# Sheet1.net
KiCad netlist of a schematic drawn in Altium Designer
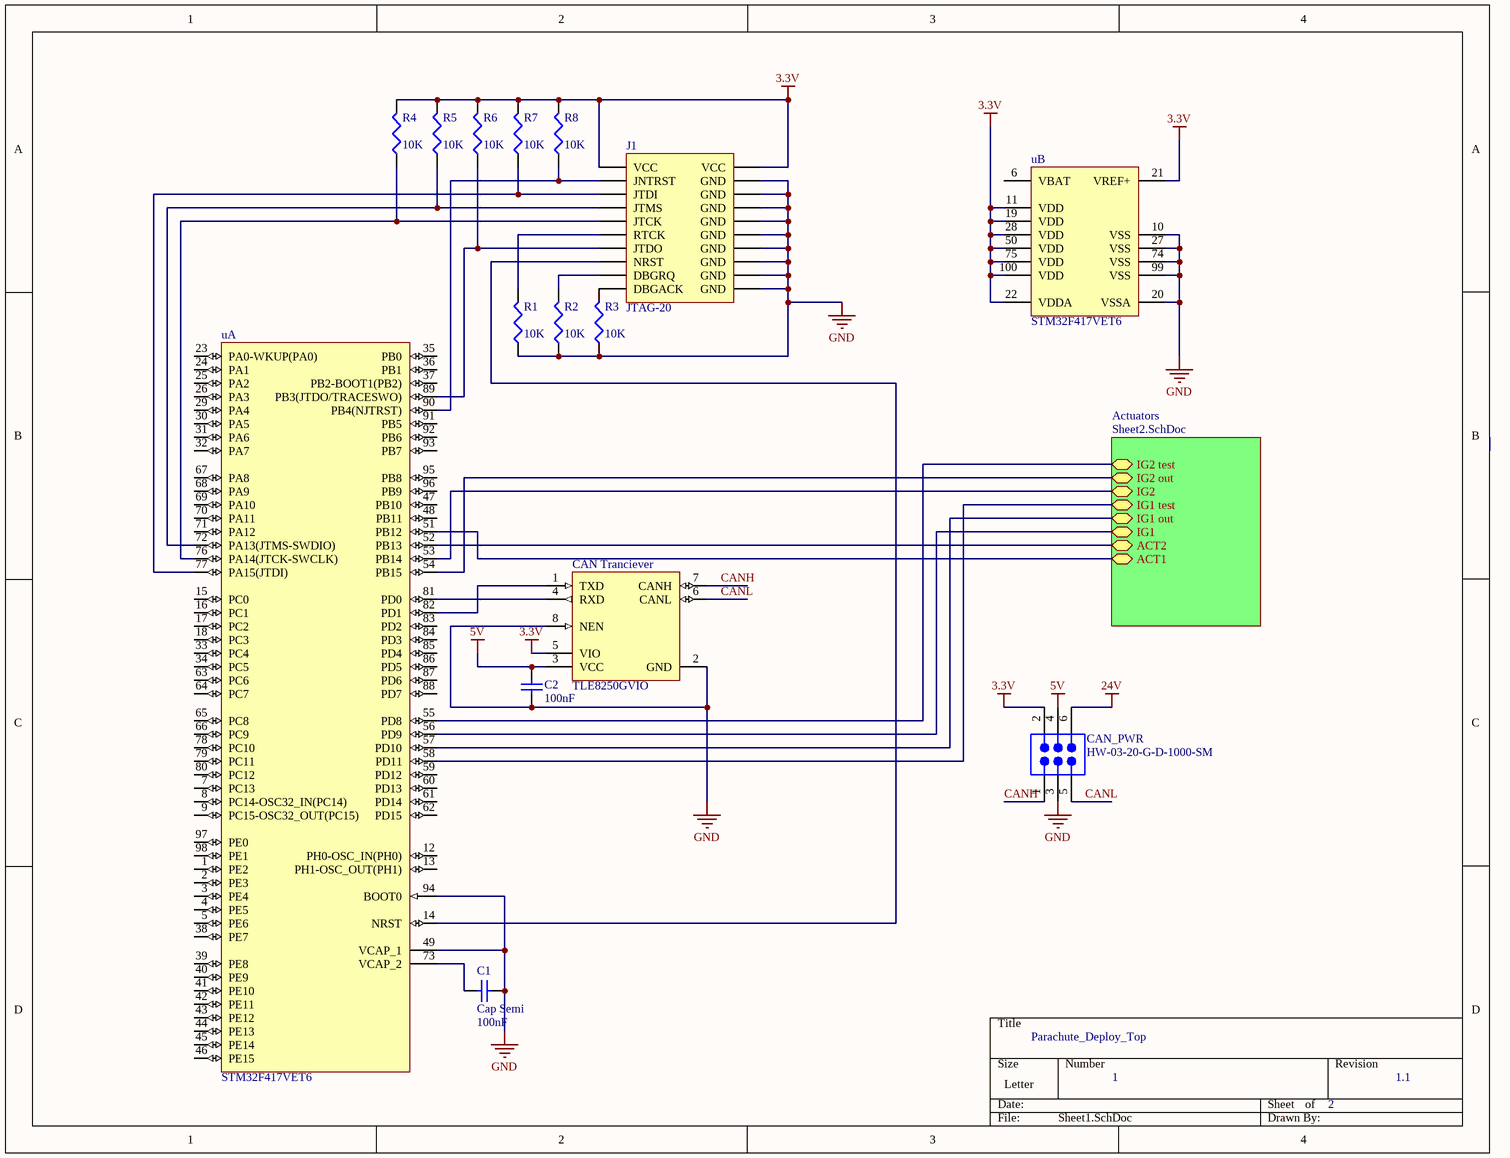
[diagram p0: Sheet1.SchDoc]

(export (version "E")
  (design (tool "Eeschema 10.0.6"))
  (components
    (comp (ref "C1")
      (value "Cap Semi")
      (footprint "C1206")
      (description "Capacitor (Semiconductor SIM Model)")
      (fields (field (name "ALTIUM_VALUE") "100nF") (field (name "PUBLISHER") "Altium Limited"))
      (libsource (lib "Miscellaneous Devices") (part "Cap Semi"))
    )
    (comp (ref "C2")
      (value "100nF")
      (footprint "C1206")
      (description "Capacitor (Semiconductor SIM Model)")
      (fields (field (name "Comment") "Cap Semi") (field (name "PUBLISHER") "Altium Limited"))
      (libsource (lib "Miscellaneous Devices") (part "Cap Semi"))
    )
    (comp (ref "CAN Tranciever")
      (value "TLE8250GVIO")
      (footprint "INF-PG-DSO-8-16_N")
      (description "High Speed CAN-Transceiver, 1 Mbit/s Transmission Rate, PG-DSO-8-16, Reel, Green")
      (fields (field (name "MANUFACTURER") "Infineon"))
      (libsource (lib "Infineon_Transceiver") (part "TLE8250GVIO"))
    )
    (comp (ref "CAN_PWR")
      (value "HW-03-20-G-D-1000-SM")
      (footprint "SMTC-HW-03-20-X-D-1000-SM")
      (fields (field (name "MANUFACTURER") "Samtec"))
      (libsource (lib "Samtec_2,54_mm_Pitch_Terminal_Strips") (part "HW-03-20-G-D-1000-SM"))
    )
    (comp (ref "J1")
      (value "JTAG-20")
      (footprint "PCBComponent_1")
      (description "20-pin JTAG header")
      (libsource (lib "Rocket_Connectors") (part "HEADER 10X2"))
    )
    (comp (ref "R1")
      (value "10K")
      (footprint "J1-0603")
      (description "Resistor")
      (fields (field (name "Comment") "RTCK PD") (field (name "PUBLISHER") "Altium Limited"))
      (libsource (lib "Miscellaneous Devices") (part "Res3"))
    )
    (comp (ref "R2")
      (value "10K")
      (footprint "J1-0603")
      (description "Resistor")
      (fields (field (name "Comment") "DBGRQ PD") (field (name "PUBLISHER") "Altium Limited"))
      (libsource (lib "Miscellaneous Devices") (part "Res3"))
    )
    (comp (ref "R3")
      (value "10K")
      (footprint "J1-0603")
      (description "Resistor")
      (fields (field (name "Comment") "DBGACK PD") (field (name "PUBLISHER") "Altium Limited"))
      (libsource (lib "Miscellaneous Devices") (part "Res3"))
    )
    (comp (ref "R4")
      (value "10K")
      (footprint "J1-0603")
      (description "Resistor")
      (fields (field (name "Comment") "RTCK PD") (field (name "PUBLISHER") "Altium Limited"))
      (libsource (lib "Miscellaneous Devices") (part "Res3"))
    )
    (comp (ref "R5")
      (value "10K")
      (footprint "J1-0603")
      (description "Resistor")
      (fields (field (name "Comment") "RTCK PD") (field (name "PUBLISHER") "Altium Limited"))
      (libsource (lib "Miscellaneous Devices") (part "Res3"))
    )
    (comp (ref "R6")
      (value "10K")
      (footprint "J1-0603")
      (description "Resistor")
      (fields (field (name "Comment") "RTCK PD") (field (name "PUBLISHER") "Altium Limited"))
      (libsource (lib "Miscellaneous Devices") (part "Res3"))
    )
    (comp (ref "R7")
      (value "10K")
      (footprint "J1-0603")
      (description "Resistor")
      (fields (field (name "Comment") "RTCK PD") (field (name "PUBLISHER") "Altium Limited"))
      (libsource (lib "Miscellaneous Devices") (part "Res3"))
    )
    (comp (ref "R8")
      (value "10K")
      (footprint "J1-0603")
      (description "Resistor")
      (fields (field (name "Comment") "RTCK PD") (field (name "PUBLISHER") "Altium Limited"))
      (libsource (lib "Miscellaneous Devices") (part "Res3"))
    )
    (comp (ref "u")
      (value "STM32F417VET6")
      (footprint "STM-LQFP100_N")
      (fields (field (name "MANUFACTURER") "STMicroelectronics"))
      (libsource (lib "STMicroelectronics STM32 F4") (part "STM32F417VET6"))
    )
  )
  (nets
    (net (code "1") (name "/ACT1") (class "Default")
      (node (ref "u") (pin "51") (pinfunction "PB12_51") (pintype "bidirectional"))
    )
    (net (code "2") (name "/ACT2") (class "Default")
      (node (ref "u") (pin "52") (pinfunction "PB13_52") (pintype "bidirectional"))
    )
    (net (code "3") (name "/CANH") (class "Default")
      (node (ref "CAN Tranciever") (pin "7") (pinfunction "CANH_7") (pintype "bidirectional"))
      (node (ref "CAN_PWR") (pin "1") (pinfunction "1_1") (pintype "passive"))
    )
    (net (code "4") (name "/CANL") (class "Default")
      (node (ref "CAN Tranciever") (pin "6") (pinfunction "CANL_6") (pintype "bidirectional"))
      (node (ref "CAN_PWR") (pin "5") (pinfunction "5_5") (pintype "passive"))
    )
    (net (code "5") (name "/IG1") (class "Default")
      (node (ref "u") (pin "56") (pinfunction "PD9_56") (pintype "bidirectional"))
    )
    (net (code "6") (name "/IG1 out") (class "Default")
      (node (ref "u") (pin "57") (pinfunction "PD10_57") (pintype "bidirectional"))
    )
    (net (code "7") (name "/IG1 test") (class "Default")
      (node (ref "u") (pin "58") (pinfunction "PD11_58") (pintype "bidirectional"))
    )
    (net (code "8") (name "/IG2") (class "Default")
      (node (ref "u") (pin "53") (pinfunction "PB14_53") (pintype "bidirectional"))
    )
    (net (code "9") (name "/IG2 out") (class "Default")
      (node (ref "u") (pin "54") (pinfunction "PB15_54") (pintype "bidirectional"))
    )
    (net (code "10") (name "/IG2 test") (class "Default")
      (node (ref "u") (pin "55") (pinfunction "PD8_55") (pintype "bidirectional"))
    )
    (net (code "11") (name "3.3V") (class "Default")
      (node (ref "CAN Tranciever") (pin "5") (pinfunction "VIO_5") (pintype "power_in"))
      (node (ref "CAN_PWR") (pin "2") (pinfunction "2_2") (pintype "passive"))
      (node (ref "J1") (pin "1") (pinfunction "VCC_1") (pintype "passive"))
      (node (ref "J1") (pin "2") (pinfunction "VCC_2") (pintype "passive"))
      (node (ref "R4") (pin "2") (pinfunction "2_2") (pintype "passive"))
      (node (ref "R5") (pin "2") (pinfunction "2_2") (pintype "passive"))
      (node (ref "R6") (pin "2") (pinfunction "2_2") (pintype "passive"))
      (node (ref "R7") (pin "2") (pinfunction "2_2") (pintype "passive"))
      (node (ref "R8") (pin "2") (pinfunction "2_2") (pintype "passive"))
      (node (ref "u") (pin "100") (pinfunction "VDD_100") (pintype "power_in"))
      (node (ref "u") (pin "11") (pinfunction "VDD_11") (pintype "power_in"))
      (node (ref "u") (pin "19") (pinfunction "VDD_19") (pintype "power_in"))
      (node (ref "u") (pin "21") (pinfunction "VREF+_21") (pintype "power_in"))
      (node (ref "u") (pin "22") (pinfunction "VDDA_22") (pintype "power_in"))
      (node (ref "u") (pin "28") (pinfunction "VDD_28") (pintype "power_in"))
      (node (ref "u") (pin "50") (pinfunction "VDD_50") (pintype "power_in"))
      (node (ref "u") (pin "75") (pinfunction "VDD_75") (pintype "power_in"))
    )
    (net (code "12") (name "5V") (class "Default")
      (node (ref "C2") (pin "2") (pinfunction "2_2") (pintype "passive"))
      (node (ref "CAN Tranciever") (pin "3") (pinfunction "VCC_3") (pintype "power_in"))
      (node (ref "CAN_PWR") (pin "4") (pinfunction "4_4") (pintype "passive"))
    )
    (net (code "13") (name "24V") (class "Default")
      (node (ref "CAN_PWR") (pin "6") (pinfunction "6_6") (pintype "passive"))
    )
    (net (code "14") (name "GND") (class "Default")
      (node (ref "C1") (pin "2") (pinfunction "2_2") (pintype "passive"))
      (node (ref "C2") (pin "1") (pinfunction "1_1") (pintype "passive"))
      (node (ref "CAN Tranciever") (pin "2") (pinfunction "GND_2") (pintype "power_in"))
      (node (ref "CAN Tranciever") (pin "8") (pinfunction "NEN_8") (pintype "input"))
      (node (ref "CAN_PWR") (pin "3") (pinfunction "3_3") (pintype "passive"))
      (node (ref "J1") (pin "10") (pinfunction "GND_10") (pintype "passive"))
      (node (ref "J1") (pin "12") (pinfunction "GND_12") (pintype "passive"))
      (node (ref "J1") (pin "14") (pinfunction "GND_14") (pintype "passive"))
      (node (ref "J1") (pin "16") (pinfunction "GND_16") (pintype "passive"))
      (node (ref "J1") (pin "18") (pinfunction "GND_18") (pintype "passive"))
      (node (ref "J1") (pin "20") (pinfunction "GND_20") (pintype "passive"))
      (node (ref "J1") (pin "4") (pinfunction "GND_4") (pintype "passive"))
      (node (ref "J1") (pin "6") (pinfunction "GND_6") (pintype "passive"))
      (node (ref "J1") (pin "8") (pinfunction "GND_8") (pintype "passive"))
      (node (ref "R1") (pin "1") (pinfunction "1_1") (pintype "passive"))
      (node (ref "R2") (pin "1") (pinfunction "1_1") (pintype "passive"))
      (node (ref "R3") (pin "1") (pinfunction "1_1") (pintype "passive"))
      (node (ref "u") (pin "10") (pinfunction "VSS_10") (pintype "power_in"))
      (node (ref "u") (pin "20") (pinfunction "VSSA_20") (pintype "power_in"))
      (node (ref "u") (pin "27") (pinfunction "VSS_27") (pintype "power_in"))
      (node (ref "u") (pin "49") (pinfunction "VCAP_1_49") (pintype "power_in"))
      (node (ref "u") (pin "74") (pinfunction "VSS_74") (pintype "power_in"))
      (node (ref "u") (pin "94") (pinfunction "BOOT0_94") (pintype "input"))
      (node (ref "u") (pin "99") (pinfunction "VSS_99") (pintype "power_in"))
    )
    (net (code "15") (name "Net-(CAN Tranciever-RXD)") (class "Default")
      (node (ref "CAN Tranciever") (pin "4") (pinfunction "RXD_4") (pintype "output"))
      (node (ref "u") (pin "81") (pinfunction "PD0_81") (pintype "bidirectional"))
    )
    (net (code "16") (name "Net-(CAN Tranciever-TXD)") (class "Default")
      (node (ref "CAN Tranciever") (pin "1") (pinfunction "TXD_1") (pintype "input"))
      (node (ref "u") (pin "82") (pinfunction "PD1_82") (pintype "bidirectional"))
    )
    (net (code "17") (name "Net-(J1-DBGACK)") (class "Default")
      (node (ref "J1") (pin "19") (pinfunction "DBGACK_19") (pintype "passive"))
      (node (ref "R3") (pin "2") (pinfunction "2_2") (pintype "passive"))
    )
    (net (code "18") (name "Net-(J1-DBGRQ)") (class "Default")
      (node (ref "J1") (pin "17") (pinfunction "DBGRQ_17") (pintype "passive"))
      (node (ref "R2") (pin "2") (pinfunction "2_2") (pintype "passive"))
    )
    (net (code "19") (name "Net-(J1-JNTRST)") (class "Default")
      (node (ref "J1") (pin "3") (pinfunction "JNTRST_3") (pintype "passive"))
      (node (ref "R8") (pin "1") (pinfunction "1_1") (pintype "passive"))
      (node (ref "u") (pin "90") (pinfunction "PB4(NJTRST)_90") (pintype "bidirectional"))
    )
    (net (code "20") (name "Net-(J1-JTCK)") (class "Default")
      (node (ref "J1") (pin "9") (pinfunction "JTCK_9") (pintype "passive"))
      (node (ref "R4") (pin "1") (pinfunction "1_1") (pintype "passive"))
      (node (ref "u") (pin "76") (pinfunction "PA14(JTCK-SWCLK)_76") (pintype "bidirectional"))
    )
    (net (code "21") (name "Net-(J1-JTDI)") (class "Default")
      (node (ref "J1") (pin "5") (pinfunction "JTDI_5") (pintype "passive"))
      (node (ref "R7") (pin "1") (pinfunction "1_1") (pintype "passive"))
      (node (ref "u") (pin "77") (pinfunction "PA15(JTDI)_77") (pintype "bidirectional"))
    )
    (net (code "22") (name "Net-(J1-JTDO)") (class "Default")
      (node (ref "J1") (pin "13") (pinfunction "JTDO_13") (pintype "passive"))
      (node (ref "R6") (pin "1") (pinfunction "1_1") (pintype "passive"))
      (node (ref "u") (pin "89") (pinfunction "PB3(JTDO/TRACESWO)_89") (pintype "bidirectional"))
    )
    (net (code "23") (name "Net-(J1-JTMS)") (class "Default")
      (node (ref "J1") (pin "7") (pinfunction "JTMS_7") (pintype "passive"))
      (node (ref "R5") (pin "1") (pinfunction "1_1") (pintype "passive"))
      (node (ref "u") (pin "72") (pinfunction "PA13(JTMS-SWDIO)_72") (pintype "bidirectional"))
    )
    (net (code "24") (name "Net-(J1-NRST)") (class "Default")
      (node (ref "J1") (pin "15") (pinfunction "NRST_15") (pintype "passive"))
      (node (ref "u") (pin "14") (pinfunction "NRST_14") (pintype "bidirectional"))
    )
    (net (code "25") (name "Net-(J1-RTCK)") (class "Default")
      (node (ref "J1") (pin "11") (pinfunction "RTCK_11") (pintype "passive"))
      (node (ref "R1") (pin "2") (pinfunction "2_2") (pintype "passive"))
    )
    (net (code "26") (name "Net-(uA-VCAP_2)") (class "Default")
      (node (ref "C1") (pin "1") (pinfunction "1_1") (pintype "passive"))
      (node (ref "u") (pin "73") (pinfunction "VCAP_2_73") (pintype "power_in"))
    )
    (net (code "27") (name "unconnected-(uA-PA0-WKUP(PA0)-Pad23)") (class "Default")
      (node (ref "u") (pin "23") (pinfunction "PA0-WKUP(PA0)_23") (pintype "bidirectional"))
    )
    (net (code "28") (name "unconnected-(uA-PA1-Pad24)") (class "Default")
      (node (ref "u") (pin "24") (pinfunction "PA1_24") (pintype "bidirectional"))
    )
    (net (code "29") (name "unconnected-(uA-PA2-Pad25)") (class "Default")
      (node (ref "u") (pin "25") (pinfunction "PA2_25") (pintype "bidirectional"))
    )
    (net (code "30") (name "unconnected-(uA-PA3-Pad26)") (class "Default")
      (node (ref "u") (pin "26") (pinfunction "PA3_26") (pintype "bidirectional"))
    )
    (net (code "31") (name "unconnected-(uA-PA4-Pad29)") (class "Default")
      (node (ref "u") (pin "29") (pinfunction "PA4_29") (pintype "bidirectional"))
    )
    (net (code "32") (name "unconnected-(uA-PA5-Pad30)") (class "Default")
      (node (ref "u") (pin "30") (pinfunction "PA5_30") (pintype "bidirectional"))
    )
    (net (code "33") (name "unconnected-(uA-PA6-Pad31)") (class "Default")
      (node (ref "u") (pin "31") (pinfunction "PA6_31") (pintype "bidirectional"))
    )
    (net (code "34") (name "unconnected-(uA-PA7-Pad32)") (class "Default")
      (node (ref "u") (pin "32") (pinfunction "PA7_32") (pintype "bidirectional"))
    )
    (net (code "35") (name "unconnected-(uA-PA8-Pad67)") (class "Default")
      (node (ref "u") (pin "67") (pinfunction "PA8_67") (pintype "bidirectional"))
    )
    (net (code "36") (name "unconnected-(uA-PA9-Pad68)") (class "Default")
      (node (ref "u") (pin "68") (pinfunction "PA9_68") (pintype "bidirectional"))
    )
    (net (code "37") (name "unconnected-(uA-PA10-Pad69)") (class "Default")
      (node (ref "u") (pin "69") (pinfunction "PA10_69") (pintype "bidirectional"))
    )
    (net (code "38") (name "unconnected-(uA-PA11-Pad70)") (class "Default")
      (node (ref "u") (pin "70") (pinfunction "PA11_70") (pintype "bidirectional"))
    )
    (net (code "39") (name "unconnected-(uA-PA12-Pad71)") (class "Default")
      (node (ref "u") (pin "71") (pinfunction "PA12_71") (pintype "bidirectional"))
    )
    (net (code "40") (name "unconnected-(uA-PB0-Pad35)") (class "Default")
      (node (ref "u") (pin "35") (pinfunction "PB0_35") (pintype "bidirectional"))
    )
    (net (code "41") (name "unconnected-(uA-PB1-Pad36)") (class "Default")
      (node (ref "u") (pin "36") (pinfunction "PB1_36") (pintype "bidirectional"))
    )
    (net (code "42") (name "unconnected-(uA-PB2-BOOT1(PB2)-Pad37)") (class "Default")
      (node (ref "u") (pin "37") (pinfunction "PB2-BOOT1(PB2)_37") (pintype "bidirectional"))
    )
    (net (code "43") (name "unconnected-(uA-PB5-Pad91)") (class "Default")
      (node (ref "u") (pin "91") (pinfunction "PB5_91") (pintype "bidirectional"))
    )
    (net (code "44") (name "unconnected-(uA-PB6-Pad92)") (class "Default")
      (node (ref "u") (pin "92") (pinfunction "PB6_92") (pintype "bidirectional"))
    )
    (net (code "45") (name "unconnected-(uA-PB7-Pad93)") (class "Default")
      (node (ref "u") (pin "93") (pinfunction "PB7_93") (pintype "bidirectional"))
    )
    (net (code "46") (name "unconnected-(uA-PB8-Pad95)") (class "Default")
      (node (ref "u") (pin "95") (pinfunction "PB8_95") (pintype "bidirectional"))
    )
    (net (code "47") (name "unconnected-(uA-PB9-Pad96)") (class "Default")
      (node (ref "u") (pin "96") (pinfunction "PB9_96") (pintype "bidirectional"))
    )
    (net (code "48") (name "unconnected-(uA-PB10-Pad47)") (class "Default")
      (node (ref "u") (pin "47") (pinfunction "PB10_47") (pintype "bidirectional"))
    )
    (net (code "49") (name "unconnected-(uA-PB11-Pad48)") (class "Default")
      (node (ref "u") (pin "48") (pinfunction "PB11_48") (pintype "bidirectional"))
    )
    (net (code "50") (name "unconnected-(uA-PC0-Pad15)") (class "Default")
      (node (ref "u") (pin "15") (pinfunction "PC0_15") (pintype "bidirectional"))
    )
    (net (code "51") (name "unconnected-(uA-PC1-Pad16)") (class "Default")
      (node (ref "u") (pin "16") (pinfunction "PC1_16") (pintype "bidirectional"))
    )
    (net (code "52") (name "unconnected-(uA-PC2-Pad17)") (class "Default")
      (node (ref "u") (pin "17") (pinfunction "PC2_17") (pintype "bidirectional"))
    )
    (net (code "53") (name "unconnected-(uA-PC3-Pad18)") (class "Default")
      (node (ref "u") (pin "18") (pinfunction "PC3_18") (pintype "bidirectional"))
    )
    (net (code "54") (name "unconnected-(uA-PC4-Pad33)") (class "Default")
      (node (ref "u") (pin "33") (pinfunction "PC4_33") (pintype "bidirectional"))
    )
    (net (code "55") (name "unconnected-(uA-PC5-Pad34)") (class "Default")
      (node (ref "u") (pin "34") (pinfunction "PC5_34") (pintype "bidirectional"))
    )
    (net (code "56") (name "unconnected-(uA-PC6-Pad63)") (class "Default")
      (node (ref "u") (pin "63") (pinfunction "PC6_63") (pintype "bidirectional"))
    )
    (net (code "57") (name "unconnected-(uA-PC7-Pad64)") (class "Default")
      (node (ref "u") (pin "64") (pinfunction "PC7_64") (pintype "bidirectional"))
    )
    (net (code "58") (name "unconnected-(uA-PC8-Pad65)") (class "Default")
      (node (ref "u") (pin "65") (pinfunction "PC8_65") (pintype "bidirectional"))
    )
    (net (code "59") (name "unconnected-(uA-PC9-Pad66)") (class "Default")
      (node (ref "u") (pin "66") (pinfunction "PC9_66") (pintype "bidirectional"))
    )
    (net (code "60") (name "unconnected-(uA-PC10-Pad78)") (class "Default")
      (node (ref "u") (pin "78") (pinfunction "PC10_78") (pintype "bidirectional"))
    )
    (net (code "61") (name "unconnected-(uA-PC11-Pad79)") (class "Default")
      (node (ref "u") (pin "79") (pinfunction "PC11_79") (pintype "bidirectional"))
    )
    (net (code "62") (name "unconnected-(uA-PC12-Pad80)") (class "Default")
      (node (ref "u") (pin "80") (pinfunction "PC12_80") (pintype "bidirectional"))
    )
    (net (code "63") (name "unconnected-(uA-PC13-Pad7)") (class "Default")
      (node (ref "u") (pin "7") (pinfunction "PC13_7") (pintype "bidirectional"))
    )
    (net (code "64") (name "unconnected-(uA-PC14-OSC32_IN(PC14)-Pad8)") (class "Default")
      (node (ref "u") (pin "8") (pinfunction "PC14-OSC32_IN(PC14)_8") (pintype "bidirectional"))
    )
    (net (code "65") (name "unconnected-(uA-PC15-OSC32_OUT(PC15)-Pad9)") (class "Default")
      (node (ref "u") (pin "9") (pinfunction "PC15-OSC32_OUT(PC15)_9") (pintype "bidirectional"))
    )
    (net (code "66") (name "unconnected-(uA-PD2-Pad83)") (class "Default")
      (node (ref "u") (pin "83") (pinfunction "PD2_83") (pintype "bidirectional"))
    )
    (net (code "67") (name "unconnected-(uA-PD3-Pad84)") (class "Default")
      (node (ref "u") (pin "84") (pinfunction "PD3_84") (pintype "bidirectional"))
    )
    (net (code "68") (name "unconnected-(uA-PD4-Pad85)") (class "Default")
      (node (ref "u") (pin "85") (pinfunction "PD4_85") (pintype "bidirectional"))
    )
    (net (code "69") (name "unconnected-(uA-PD5-Pad86)") (class "Default")
      (node (ref "u") (pin "86") (pinfunction "PD5_86") (pintype "bidirectional"))
    )
    (net (code "70") (name "unconnected-(uA-PD6-Pad87)") (class "Default")
      (node (ref "u") (pin "87") (pinfunction "PD6_87") (pintype "bidirectional"))
    )
    (net (code "71") (name "unconnected-(uA-PD7-Pad88)") (class "Default")
      (node (ref "u") (pin "88") (pinfunction "PD7_88") (pintype "bidirectional"))
    )
    (net (code "72") (name "unconnected-(uA-PD12-Pad59)") (class "Default")
      (node (ref "u") (pin "59") (pinfunction "PD12_59") (pintype "bidirectional"))
    )
    (net (code "73") (name "unconnected-(uA-PD13-Pad60)") (class "Default")
      (node (ref "u") (pin "60") (pinfunction "PD13_60") (pintype "bidirectional"))
    )
    (net (code "74") (name "unconnected-(uA-PD14-Pad61)") (class "Default")
      (node (ref "u") (pin "61") (pinfunction "PD14_61") (pintype "bidirectional"))
    )
    (net (code "75") (name "unconnected-(uA-PD15-Pad62)") (class "Default")
      (node (ref "u") (pin "62") (pinfunction "PD15_62") (pintype "bidirectional"))
    )
    (net (code "76") (name "unconnected-(uA-PE0-Pad97)") (class "Default")
      (node (ref "u") (pin "97") (pinfunction "PE0_97") (pintype "bidirectional"))
    )
    (net (code "77") (name "unconnected-(uA-PE1-Pad98)") (class "Default")
      (node (ref "u") (pin "98") (pinfunction "PE1_98") (pintype "bidirectional"))
    )
    (net (code "78") (name "unconnected-(uA-PE2-Pad1)") (class "Default")
      (node (ref "u") (pin "1") (pinfunction "PE2_1") (pintype "bidirectional"))
    )
    (net (code "79") (name "unconnected-(uA-PE3-Pad2)") (class "Default")
      (node (ref "u") (pin "2") (pinfunction "PE3_2") (pintype "bidirectional"))
    )
    (net (code "80") (name "unconnected-(uA-PE4-Pad3)") (class "Default")
      (node (ref "u") (pin "3") (pinfunction "PE4_3") (pintype "bidirectional"))
    )
    (net (code "81") (name "unconnected-(uA-PE5-Pad4)") (class "Default")
      (node (ref "u") (pin "4") (pinfunction "PE5_4") (pintype "bidirectional"))
    )
    (net (code "82") (name "unconnected-(uA-PE6-Pad5)") (class "Default")
      (node (ref "u") (pin "5") (pinfunction "PE6_5") (pintype "bidirectional"))
    )
    (net (code "83") (name "unconnected-(uA-PE7-Pad38)") (class "Default")
      (node (ref "u") (pin "38") (pinfunction "PE7_38") (pintype "bidirectional"))
    )
    (net (code "84") (name "unconnected-(uA-PE8-Pad39)") (class "Default")
      (node (ref "u") (pin "39") (pinfunction "PE8_39") (pintype "bidirectional"))
    )
    (net (code "85") (name "unconnected-(uA-PE9-Pad40)") (class "Default")
      (node (ref "u") (pin "40") (pinfunction "PE9_40") (pintype "bidirectional"))
    )
    (net (code "86") (name "unconnected-(uA-PE10-Pad41)") (class "Default")
      (node (ref "u") (pin "41") (pinfunction "PE10_41") (pintype "bidirectional"))
    )
    (net (code "87") (name "unconnected-(uA-PE11-Pad42)") (class "Default")
      (node (ref "u") (pin "42") (pinfunction "PE11_42") (pintype "bidirectional"))
    )
    (net (code "88") (name "unconnected-(uA-PE12-Pad43)") (class "Default")
      (node (ref "u") (pin "43") (pinfunction "PE12_43") (pintype "bidirectional"))
    )
    (net (code "89") (name "unconnected-(uA-PE13-Pad44)") (class "Default")
      (node (ref "u") (pin "44") (pinfunction "PE13_44") (pintype "bidirectional"))
    )
    (net (code "90") (name "unconnected-(uA-PE14-Pad45)") (class "Default")
      (node (ref "u") (pin "45") (pinfunction "PE14_45") (pintype "bidirectional"))
    )
    (net (code "91") (name "unconnected-(uA-PE15-Pad46)") (class "Default")
      (node (ref "u") (pin "46") (pinfunction "PE15_46") (pintype "bidirectional"))
    )
    (net (code "92") (name "unconnected-(uA-PH0-OSC_IN(PH0)-Pad12)") (class "Default")
      (node (ref "u") (pin "12") (pinfunction "PH0-OSC_IN(PH0)_12") (pintype "bidirectional"))
    )
    (net (code "93") (name "unconnected-(uA-PH1-OSC_OUT(PH1)-Pad13)") (class "Default")
      (node (ref "u") (pin "13") (pinfunction "PH1-OSC_OUT(PH1)_13") (pintype "bidirectional"))
    )
    (net (code "94") (name "unconnected-(uB-VBAT-Pad6)") (class "Default")
      (node (ref "u") (pin "6") (pinfunction "VBAT_6") (pintype "power_in"))
    )
  )
)
